# M_2_Key_A_E.net
KiCad netlist of a schematic drawn in Altium Designer
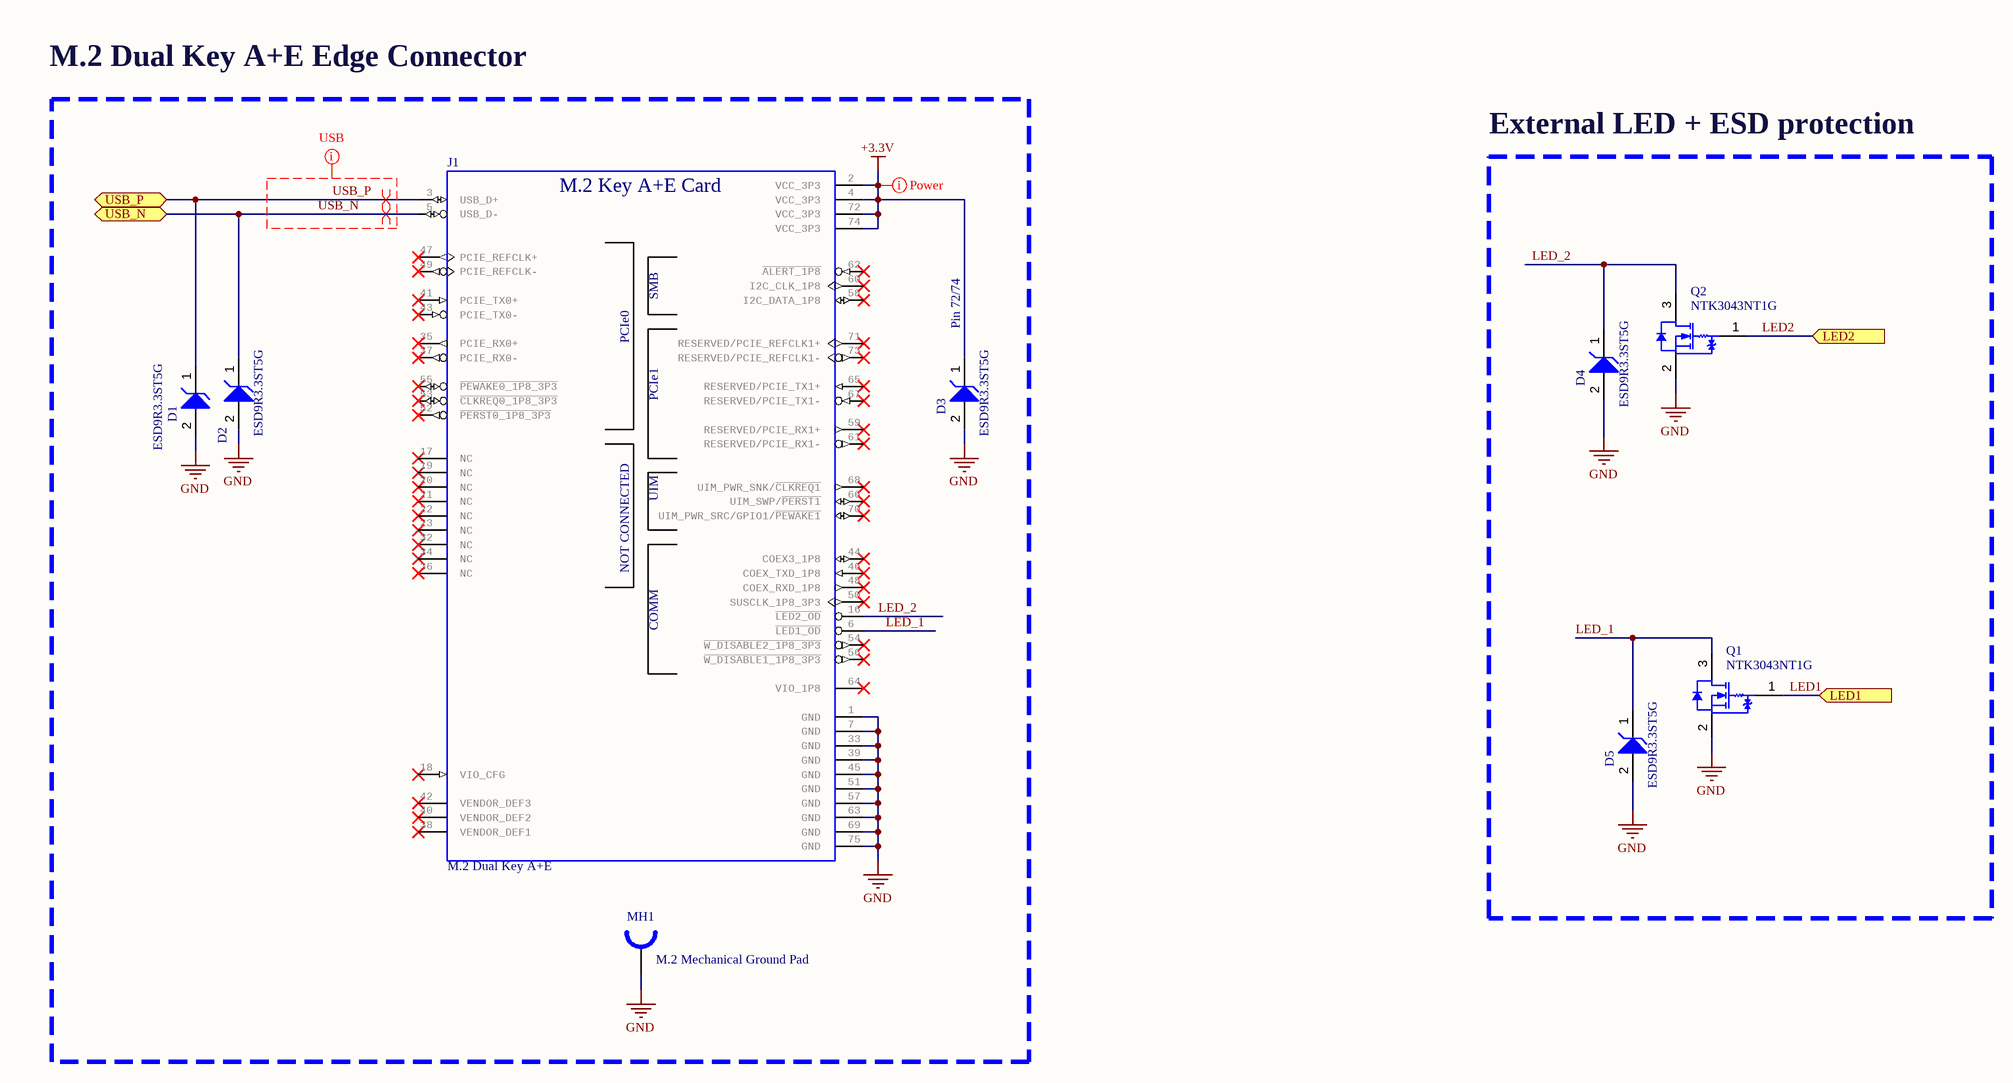
[diagram p0: M.2_Key_A+E.SchDoc]

(export (version "E")
  (design (tool "Eeschema 10.0.6"))
  (components
    (comp (ref "D1")
      (value "ESD9R3.3ST5G")
      (footprint "ONSC-SOD-923-2-514AB-01_V")
      (description "ESD9R3.3S Series 4.8 V 0.5 pF Uni-Directional ESD Protection Diode - SOD-923")
      (libsource (lib "ANavS GmbH") (part "ONSC-K1A2-2_A"))
    )
    (comp (ref "D2")
      (value "ESD9R3.3ST5G")
      (footprint "ONSC-SOD-923-2-514AB-01_V")
      (description "ESD9R3.3S Series 4.8 V 0.5 pF Uni-Directional ESD Protection Diode - SOD-923")
      (libsource (lib "ANavS GmbH") (part "ONSC-K1A2-2_A"))
    )
    (comp (ref "D3")
      (value "ESD9R3.3ST5G")
      (footprint "ONSC-SOD-923-2-514AB-01_V")
      (description "ESD9R3.3S Series 4.8 V 0.5 pF Uni-Directional ESD Protection Diode - SOD-923")
      (libsource (lib "ANavS GmbH") (part "ONSC-K1A2-2_A"))
    )
    (comp (ref "D4")
      (value "ESD9R3.3ST5G")
      (footprint "ONSC-SOD-923-2-514AB-01_V")
      (description "ESD9R3.3S Series 4.8 V 0.5 pF Uni-Directional ESD Protection Diode - SOD-923")
      (libsource (lib "ANavS GmbH") (part "ONSC-K1A2-2_A"))
    )
    (comp (ref "D5")
      (value "ESD9R3.3ST5G")
      (footprint "ONSC-SOD-923-2-514AB-01_V")
      (description "ESD9R3.3S Series 4.8 V 0.5 pF Uni-Directional ESD Protection Diode - SOD-923")
      (libsource (lib "ANavS GmbH") (part "ONSC-K1A2-2_A"))
    )
    (comp (ref "J1")
      (value "M.2 Dual Key A+E")
      (footprint "M.2 Key A+E card-Footprint")
      (description "Golden finger, M.2 Key A+E, Dual, Staggered, Pitch 0.5mm")
      (libsource (lib "ANavS GmbH") (part "M.2_KeyA+E_card-Symbol"))
    )
    (comp (ref "MH1")
      (value "M.2 Mechanical Ground Pad")
      (footprint "M.2 Mechanical Ground Pad Footprint")
      (libsource (lib "ANavS GmbH") (part "Mounting Hole"))
    )
    (comp (ref "Q1")
      (value "NTK3043NT1G")
      (footprint "ONSC-SOT-723-3-631AA-01_V")
      (description "Single N-Channel Small Signal MOSFET with ESD Protection 20V, 285mA, 3.4Ω")
      (libsource (lib "ANavS GmbH") (part "ONSC-NMOS-G1S2D3-3_H"))
    )
    (comp (ref "Q2")
      (value "NTK3043NT1G")
      (footprint "ONSC-SOT-723-3-631AA-01_V")
      (description "Single N-Channel Small Signal MOSFET with ESD Protection 20V, 285mA, 3.4Ω")
      (libsource (lib "ANavS GmbH") (part "ONSC-NMOS-G1S2D3-3_H"))
    )
  )
  (nets
    (net (code "1") (name "+3.3V") (class "Default")
      (node (ref "D3") (pin "1") (pinfunction "K_1") (pintype "passive"))
      (node (ref "J1") (pin "2") (pinfunction "VCC_3P3_2") (pintype "power_in"))
      (node (ref "J1") (pin "4") (pinfunction "VCC_3P3_4") (pintype "power_in"))
      (node (ref "J1") (pin "72") (pinfunction "VCC_3P3_72") (pintype "power_in"))
      (node (ref "J1") (pin "74") (pinfunction "VCC_3P3_74") (pintype "power_in"))
    )
    (net (code "2") (name "/LED1") (class "Default")
      (node (ref "Q1") (pin "1") (pinfunction "G_1") (pintype "passive"))
    )
    (net (code "3") (name "/LED2") (class "Default")
      (node (ref "Q2") (pin "1") (pinfunction "G_1") (pintype "passive"))
    )
    (net (code "4") (name "/LED_1") (class "Default")
      (node (ref "D5") (pin "1") (pinfunction "K_1") (pintype "passive"))
      (node (ref "J1") (pin "6") (pinfunction "LED1_OD_6") (pintype "open_collector"))
      (node (ref "Q1") (pin "3") (pinfunction "D_3") (pintype "passive"))
    )
    (net (code "5") (name "/LED_2") (class "Default")
      (node (ref "D4") (pin "1") (pinfunction "K_1") (pintype "passive"))
      (node (ref "J1") (pin "16") (pinfunction "LED2_OD_16") (pintype "open_collector"))
      (node (ref "Q2") (pin "3") (pinfunction "D_3") (pintype "passive"))
    )
    (net (code "6") (name "/USB_N") (class "Default")
      (node (ref "D2") (pin "1") (pinfunction "K_1") (pintype "passive"))
      (node (ref "J1") (pin "5") (pinfunction "USB_D-_5") (pintype "bidirectional"))
    )
    (net (code "7") (name "/USB_P") (class "Default")
      (node (ref "D1") (pin "1") (pinfunction "K_1") (pintype "passive"))
      (node (ref "J1") (pin "3") (pinfunction "USB_D+_3") (pintype "bidirectional"))
    )
    (net (code "8") (name "GND") (class "Default")
      (node (ref "D1") (pin "2") (pinfunction "A_2") (pintype "passive"))
      (node (ref "D2") (pin "2") (pinfunction "A_2") (pintype "passive"))
      (node (ref "D3") (pin "2") (pinfunction "A_2") (pintype "passive"))
      (node (ref "D4") (pin "2") (pinfunction "A_2") (pintype "passive"))
      (node (ref "D5") (pin "2") (pinfunction "A_2") (pintype "passive"))
      (node (ref "J1") (pin "1") (pinfunction "GND_1") (pintype "power_in"))
      (node (ref "J1") (pin "33") (pinfunction "GND_33") (pintype "power_in"))
      (node (ref "J1") (pin "39") (pinfunction "GND_39") (pintype "power_in"))
      (node (ref "J1") (pin "45") (pinfunction "GND_45") (pintype "power_in"))
      (node (ref "J1") (pin "51") (pinfunction "GND_51") (pintype "power_in"))
      (node (ref "J1") (pin "57") (pinfunction "GND_57") (pintype "power_in"))
      (node (ref "J1") (pin "63") (pinfunction "GND_63") (pintype "power_in"))
      (node (ref "J1") (pin "69") (pinfunction "GND_69") (pintype "power_in"))
      (node (ref "J1") (pin "7") (pinfunction "GND_7") (pintype "power_in"))
      (node (ref "J1") (pin "75") (pinfunction "GND_75") (pintype "power_in"))
      (node (ref "MH1") (pin "0") (pinfunction "Chassis_0") (pintype "passive"))
      (node (ref "Q1") (pin "2") (pinfunction "S_2") (pintype "passive"))
      (node (ref "Q2") (pin "2") (pinfunction "S_2") (pintype "passive"))
    )
    (net (code "9") (name "unconnected-(J1-ALERT_1P8-Pad62)") (class "Default")
      (node (ref "J1") (pin "62") (pinfunction "ALERT_1P8_62") (pintype "input+no_connect"))
    )
    (net (code "10") (name "unconnected-(J1-CLKREQ0_1P8_3P3-Pad53)") (class "Default")
      (node (ref "J1") (pin "53") (pinfunction "CLKREQ0_1P8_3P3_53") (pintype "bidirectional+no_connect"))
    )
    (net (code "11") (name "unconnected-(J1-COEX3_1P8-Pad44)") (class "Default")
      (node (ref "J1") (pin "44") (pinfunction "COEX3_1P8_44") (pintype "bidirectional+no_connect"))
    )
    (net (code "12") (name "unconnected-(J1-COEX_RXD_1P8-Pad48)") (class "Default")
      (node (ref "J1") (pin "48") (pinfunction "COEX_RXD_1P8_48") (pintype "output+no_connect"))
    )
    (net (code "13") (name "unconnected-(J1-COEX_TXD_1P8-Pad46)") (class "Default")
      (node (ref "J1") (pin "46") (pinfunction "COEX_TXD_1P8_46") (pintype "input+no_connect"))
    )
    (net (code "14") (name "unconnected-(J1-I2C_CLK_1P8-Pad60)") (class "Default")
      (node (ref "J1") (pin "60") (pinfunction "I2C_CLK_1P8_60") (pintype "output+no_connect"))
    )
    (net (code "15") (name "unconnected-(J1-I2C_DATA_1P8-Pad58)") (class "Default")
      (node (ref "J1") (pin "58") (pinfunction "I2C_DATA_1P8_58") (pintype "bidirectional+no_connect"))
    )
    (net (code "16") (name "unconnected-(J1-NC-Pad17)") (class "Default")
      (node (ref "J1") (pin "17") (pinfunction "NC_17") (pintype "passive+no_connect"))
    )
    (net (code "17") (name "unconnected-(J1-NC-Pad19)") (class "Default")
      (node (ref "J1") (pin "19") (pinfunction "NC_19") (pintype "passive+no_connect"))
    )
    (net (code "18") (name "unconnected-(J1-NC-Pad20)") (class "Default")
      (node (ref "J1") (pin "20") (pinfunction "NC_20") (pintype "passive+no_connect"))
    )
    (net (code "19") (name "unconnected-(J1-NC-Pad21)") (class "Default")
      (node (ref "J1") (pin "21") (pinfunction "NC_21") (pintype "passive+no_connect"))
    )
    (net (code "20") (name "unconnected-(J1-NC-Pad22)") (class "Default")
      (node (ref "J1") (pin "22") (pinfunction "NC_22") (pintype "passive+no_connect"))
    )
    (net (code "21") (name "unconnected-(J1-NC-Pad23)") (class "Default")
      (node (ref "J1") (pin "23") (pinfunction "NC_23") (pintype "passive+no_connect"))
    )
    (net (code "22") (name "unconnected-(J1-NC-Pad32)") (class "Default")
      (node (ref "J1") (pin "32") (pinfunction "NC_32") (pintype "passive+no_connect"))
    )
    (net (code "23") (name "unconnected-(J1-NC-Pad34)") (class "Default")
      (node (ref "J1") (pin "34") (pinfunction "NC_34") (pintype "passive+no_connect"))
    )
    (net (code "24") (name "unconnected-(J1-NC-Pad36)") (class "Default")
      (node (ref "J1") (pin "36") (pinfunction "NC_36") (pintype "passive+no_connect"))
    )
    (net (code "25") (name "unconnected-(J1-PCIE_REFCLK+-Pad47)") (class "Default")
      (node (ref "J1") (pin "47") (pinfunction "PCIE_REFCLK+_47") (pintype "output+no_connect"))
    )
    (net (code "26") (name "unconnected-(J1-PCIE_REFCLK--Pad49)") (class "Default")
      (node (ref "J1") (pin "49") (pinfunction "PCIE_REFCLK-_49") (pintype "output+no_connect"))
    )
    (net (code "27") (name "unconnected-(J1-PCIE_RX0+-Pad35)") (class "Default")
      (node (ref "J1") (pin "35") (pinfunction "PCIE_RX0+_35") (pintype "output+no_connect"))
    )
    (net (code "28") (name "unconnected-(J1-PCIE_RX0--Pad37)") (class "Default")
      (node (ref "J1") (pin "37") (pinfunction "PCIE_RX0-_37") (pintype "output+no_connect"))
    )
    (net (code "29") (name "unconnected-(J1-PCIE_TX0+-Pad41)") (class "Default")
      (node (ref "J1") (pin "41") (pinfunction "PCIE_TX0+_41") (pintype "input+no_connect"))
    )
    (net (code "30") (name "unconnected-(J1-PCIE_TX0--Pad43)") (class "Default")
      (node (ref "J1") (pin "43") (pinfunction "PCIE_TX0-_43") (pintype "input+no_connect"))
    )
    (net (code "31") (name "unconnected-(J1-PERST0_1P8_3P3-Pad52)") (class "Default")
      (node (ref "J1") (pin "52") (pinfunction "PERST0_1P8_3P3_52") (pintype "output+no_connect"))
    )
    (net (code "32") (name "unconnected-(J1-PEWAKE0_1P8_3P3-Pad55)") (class "Default")
      (node (ref "J1") (pin "55") (pinfunction "PEWAKE0_1P8_3P3_55") (pintype "bidirectional+no_connect"))
    )
    (net (code "33") (name "unconnected-(J1-RESERVED{slash}PCIE_REFCLK1+-Pad71)") (class "Default")
      (node (ref "J1") (pin "71") (pinfunction "RESERVED/PCIE_REFCLK1+_71") (pintype "output+no_connect"))
    )
    (net (code "34") (name "unconnected-(J1-RESERVED{slash}PCIE_REFCLK1--Pad73)") (class "Default")
      (node (ref "J1") (pin "73") (pinfunction "RESERVED/PCIE_REFCLK1-_73") (pintype "output+no_connect"))
    )
    (net (code "35") (name "unconnected-(J1-RESERVED{slash}PCIE_RX1+-Pad59)") (class "Default")
      (node (ref "J1") (pin "59") (pinfunction "RESERVED/PCIE_RX1+_59") (pintype "output+no_connect"))
    )
    (net (code "36") (name "unconnected-(J1-RESERVED{slash}PCIE_RX1--Pad61)") (class "Default")
      (node (ref "J1") (pin "61") (pinfunction "RESERVED/PCIE_RX1-_61") (pintype "output+no_connect"))
    )
    (net (code "37") (name "unconnected-(J1-RESERVED{slash}PCIE_TX1+-Pad65)") (class "Default")
      (node (ref "J1") (pin "65") (pinfunction "RESERVED/PCIE_TX1+_65") (pintype "input+no_connect"))
    )
    (net (code "38") (name "unconnected-(J1-RESERVED{slash}PCIE_TX1--Pad67)") (class "Default")
      (node (ref "J1") (pin "67") (pinfunction "RESERVED/PCIE_TX1-_67") (pintype "input+no_connect"))
    )
    (net (code "39") (name "unconnected-(J1-SUSCLK_1P8_3P3-Pad50)") (class "Default")
      (node (ref "J1") (pin "50") (pinfunction "SUSCLK_1P8_3P3_50") (pintype "output+no_connect"))
    )
    (net (code "40") (name "unconnected-(J1-UIM_PWR_SNK{slash}~{CLKREQ1}-Pad68)") (class "Default")
      (node (ref "J1") (pin "68") (pinfunction "UIM_PWR_SNK/~{CLKREQ1}_68") (pintype "output+no_connect"))
    )
    (net (code "41") (name "unconnected-(J1-UIM_PWR_SRC{slash}GPIO1{slash}~{PEWAKE1}-Pad70)") (class "Default")
      (node (ref "J1") (pin "70") (pinfunction "UIM_PWR_SRC/GPIO1/~{PEWAKE1}_70") (pintype "bidirectional+no_connect"))
    )
    (net (code "42") (name "unconnected-(J1-UIM_SWP{slash}~{PERST1}-Pad66)") (class "Default")
      (node (ref "J1") (pin "66") (pinfunction "UIM_SWP/~{PERST1}_66") (pintype "bidirectional+no_connect"))
    )
    (net (code "43") (name "unconnected-(J1-VENDOR_DEF1-Pad38)") (class "Default")
      (node (ref "J1") (pin "38") (pinfunction "VENDOR_DEF1_38") (pintype "passive+no_connect"))
    )
    (net (code "44") (name "unconnected-(J1-VENDOR_DEF2-Pad40)") (class "Default")
      (node (ref "J1") (pin "40") (pinfunction "VENDOR_DEF2_40") (pintype "passive+no_connect"))
    )
    (net (code "45") (name "unconnected-(J1-VENDOR_DEF3-Pad42)") (class "Default")
      (node (ref "J1") (pin "42") (pinfunction "VENDOR_DEF3_42") (pintype "passive+no_connect"))
    )
    (net (code "46") (name "unconnected-(J1-VIO_1P8-Pad64)") (class "Default")
      (node (ref "J1") (pin "64") (pinfunction "VIO_1P8_64") (pintype "power_in+no_connect"))
    )
    (net (code "47") (name "unconnected-(J1-VIO_CFG-Pad18)") (class "Default")
      (node (ref "J1") (pin "18") (pinfunction "VIO_CFG_18") (pintype "input+no_connect"))
    )
    (net (code "48") (name "unconnected-(J1-W_DISABLE1_1P8_3P3-Pad56)") (class "Default")
      (node (ref "J1") (pin "56") (pinfunction "W_DISABLE1_1P8_3P3_56") (pintype "output+no_connect"))
    )
    (net (code "49") (name "unconnected-(J1-W_DISABLE2_1P8_3P3-Pad54)") (class "Default")
      (node (ref "J1") (pin "54") (pinfunction "W_DISABLE2_1P8_3P3_54") (pintype "output+no_connect"))
    )
  )
)
